# Thermal_MGT.net
KiCad netlist of a schematic drawn in Altium Designer
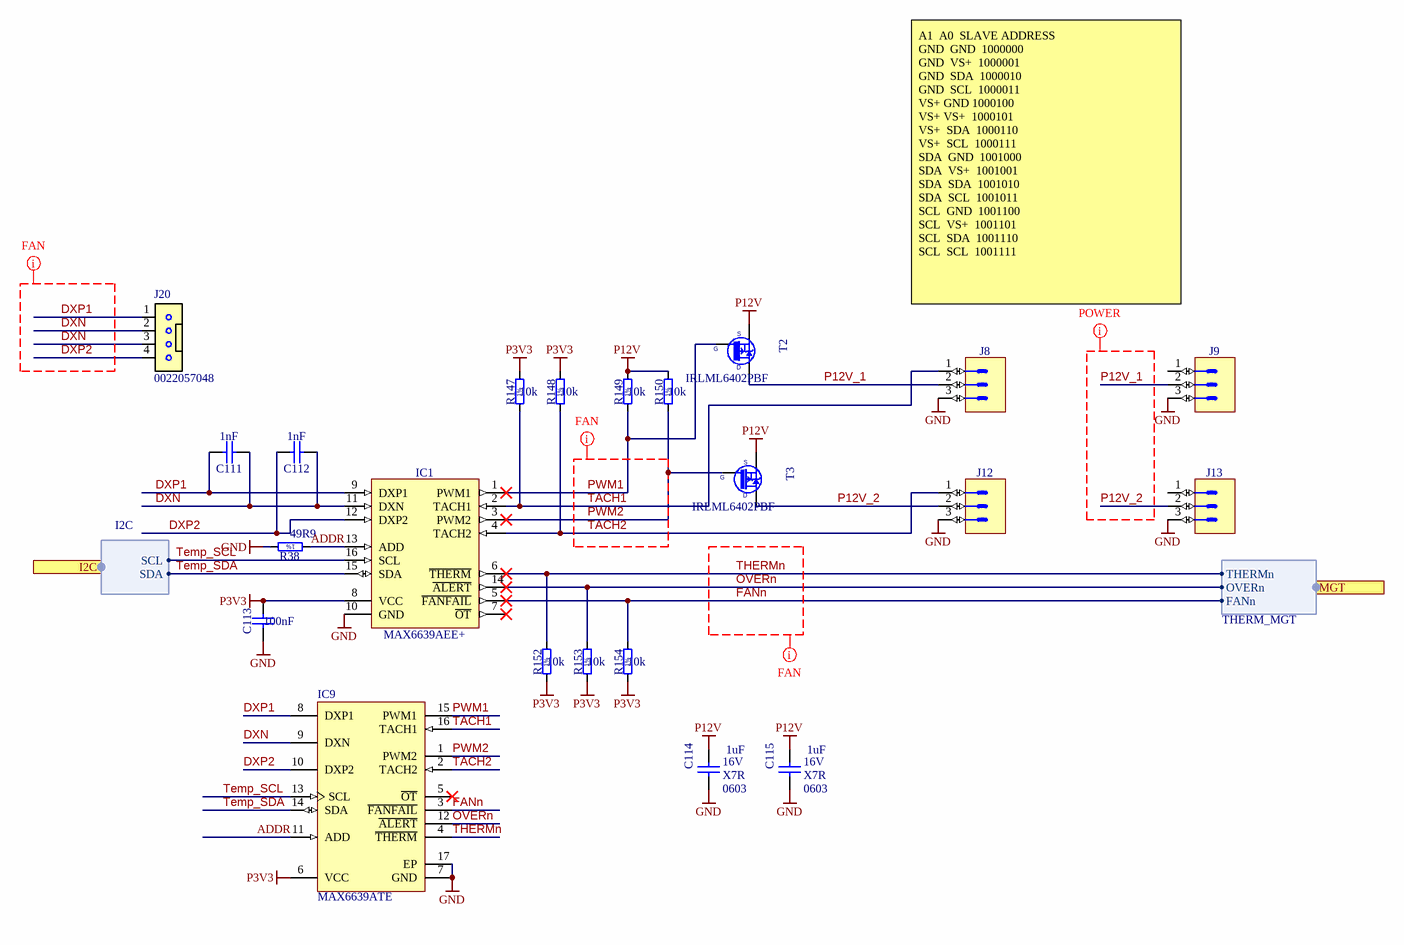
[diagram p0: Thermal_MGT.SchDoc]

(export (version "E")
  (design (tool "Eeschema 10.0.6"))
  (components
    (comp (ref "C111")
      (value "1nF")
      (footprint "CAPC1005X55N")
      (description "Non-polarised capacitor")
      (fields
        (field (name "PART NUMBER") "CC0402_1NF_50V_10%_X7R")
        (field (name "VOLTAGE") "50V")
        (field (name "AUTHOR") "CERN DEM JLC")
      )
      (libsource (lib "Capacitors") (part "Capacitor - non polarized"))
    )
    (comp (ref "C112")
      (value "1nF")
      (footprint "CAPC1005X55N")
      (description "Non-polarised capacitor")
      (fields
        (field (name "PART NUMBER") "CC0402_1NF_50V_10%_X7R")
        (field (name "VOLTAGE") "50V")
        (field (name "AUTHOR") "CERN DEM JLC")
      )
      (libsource (lib "Capacitors") (part "Capacitor - non polarized"))
    )
    (comp (ref "C113")
      (value "100nF")
      (footprint "CAPC1005X55N")
      (description "Non-polarised capacitor")
      (fields
        (field (name "PART NUMBER") "CC0402_100NF_16V_10%_X5R")
        (field (name "VOLTAGE") "16V")
        (field (name "AUTHOR") "CERN DEM JLC")
      )
      (libsource (lib "Capacitors") (part "Capacitor - non polarized"))
    )
    (comp (ref "C114")
      (value "1uF")
      (footprint "CAPC1608X87N")
      (description "Non-polarised capacitor")
      (fields
        (field (name "PART NUMBER") "CC0603_1UF_16V_10%_X7R")
        (field (name "VOLTAGE") "16V")
        (field (name "TC") "X7R")
        (field (name "TOLERANCE") "±10%")
        (field (name "CASE") "0603")
        (field (name "AUTHOR") "CERN DEM JLC")
      )
      (libsource (lib "Capacitors") (part "Capacitor - non polarized"))
    )
    (comp (ref "C115")
      (value "1uF")
      (footprint "CAPC1608X87N")
      (description "Non-polarised capacitor")
      (fields
        (field (name "PART NUMBER") "CC0603_1UF_16V_10%_X7R")
        (field (name "VOLTAGE") "16V")
        (field (name "TC") "X7R")
        (field (name "TOLERANCE") "±10%")
        (field (name "CASE") "0603")
        (field (name "AUTHOR") "CERN DEM JLC")
      )
      (libsource (lib "Capacitors") (part "Capacitor - non polarized"))
    )
    (comp (ref "IC1")
      (value "MAX6639AEE+")
      (footprint "SOP63P600X175-16N")
      (description "2-Channel Temperature Monitor with Dual, Automatic, PWM Fan-Speed Controller")
      (fields (field (name "MANUFACTURER") "MAXIM") (field (name "AUTHOR") "CERN DEM JLC"))
      (libsource (lib "ICs And Semiconductors") (part "MAX6639AEE+"))
    )
    (comp (ref "IC9")
      (value "MAX6639ATE")
      (footprint "MAXM-T1655-3_N")
      (fields (field (name "GENERIC PART NUMBER") "MAX6639"))
      (libsource (lib "Altium Content Vault") (part "MAX6639-T1655X3"))
    )
    (comp (ref "J8")
      (value "KK®")
      (footprint "MOLEX_22-05-7038")
      (description "Connector 3 Male")
      (fields
        (field (name "PART NUMBER") "MOLEX_22-05-7038")
        (field (name "MANUFACTURER") "MOLEX")
        (field (name "AUTHOR") "CERN DEM JLC")
      )
      (libsource (lib "Connectors") (part "Connector 3 Male"))
    )
    (comp (ref "J9")
      (value "KK®")
      (footprint "MOLEX_22-05-7038")
      (description "Connector 3 Male")
      (fields
        (field (name "PART NUMBER") "MOLEX_22-05-7038")
        (field (name "MANUFACTURER") "MOLEX")
        (field (name "AUTHOR") "CERN DEM JLC")
      )
      (libsource (lib "Connectors") (part "Connector 3 Male"))
    )
    (comp (ref "J12")
      (value "KK®")
      (footprint "MOLEX_22-05-7038")
      (description "Connector 3 Male")
      (fields
        (field (name "PART NUMBER") "MOLEX_22-05-7038")
        (field (name "MANUFACTURER") "MOLEX")
        (field (name "AUTHOR") "CERN DEM JLC")
      )
      (libsource (lib "Connectors") (part "Connector 3 Male"))
    )
    (comp (ref "J13")
      (value "KK®")
      (footprint "MOLEX_22-05-7038")
      (description "Connector 3 Male")
      (fields
        (field (name "PART NUMBER") "MOLEX_22-05-7038")
        (field (name "MANUFACTURER") "MOLEX")
        (field (name "AUTHOR") "CERN DEM JLC")
      )
      (libsource (lib "Connectors") (part "Connector 3 Male"))
    )
    (comp (ref "J20")
      (value "0022057048")
      (footprint "CON_0022057048")
      (description "2.54mm crimped terminal header")
      (libsource (lib "Connectors") (part "CON_4_2.54_RA_key"))
    )
    (comp (ref "R38")
      (value "49R9")
      (footprint "RESC1005X40N")
      (description "Resistor - 1%")
      (fields
        (field (name "PART NUMBER") "R0402_49R9_1%_0.0625W_100PPM")
        (field (name "POWER") "0.0625W")
        (field (name "AUTHOR") "CERN DEM JLC")
      )
      (libsource (lib "Resistors") (part "Resistor - 1%"))
    )
    (comp (ref "R147")
      (value "10k")
      (footprint "RESC1005X40N")
      (description "Resistor - 1%")
      (fields
        (field (name "PART NUMBER") "R0402_10K_1%_0.0625W_100PPM")
        (field (name "POWER") "0.0625W")
        (field (name "AUTHOR") "CERN DEM JLC")
      )
      (libsource (lib "Resistors") (part "Resistor - 1%"))
    )
    (comp (ref "R148")
      (value "10k")
      (footprint "RESC1005X40N")
      (description "Resistor - 1%")
      (fields
        (field (name "PART NUMBER") "R0402_10K_1%_0.0625W_100PPM")
        (field (name "POWER") "0.0625W")
        (field (name "AUTHOR") "CERN DEM JLC")
      )
      (libsource (lib "Resistors") (part "Resistor - 1%"))
    )
    (comp (ref "R149")
      (value "10k")
      (footprint "RESC1005X40N")
      (description "Resistor - 1%")
      (fields
        (field (name "PART NUMBER") "R0402_10K_1%_0.0625W_100PPM")
        (field (name "POWER") "0.0625W")
        (field (name "AUTHOR") "CERN DEM JLC")
      )
      (libsource (lib "Resistors") (part "Resistor - 1%"))
    )
    (comp (ref "R150")
      (value "10k")
      (footprint "RESC1005X40N")
      (description "Resistor - 1%")
      (fields
        (field (name "PART NUMBER") "R0402_10K_1%_0.0625W_100PPM")
        (field (name "POWER") "0.0625W")
        (field (name "AUTHOR") "CERN DEM JLC")
      )
      (libsource (lib "Resistors") (part "Resistor - 1%"))
    )
    (comp (ref "R152")
      (value "10k")
      (footprint "RESC1005X40N")
      (description "Resistor - 1%")
      (fields
        (field (name "PART NUMBER") "R0402_10K_1%_0.0625W_100PPM")
        (field (name "POWER") "0.0625W")
        (field (name "AUTHOR") "CERN DEM JLC")
      )
      (libsource (lib "Resistors") (part "Resistor - 1%"))
    )
    (comp (ref "R153")
      (value "10k")
      (footprint "RESC1005X40N")
      (description "Resistor - 1%")
      (fields
        (field (name "PART NUMBER") "R0402_10K_1%_0.0625W_100PPM")
        (field (name "POWER") "0.0625W")
        (field (name "AUTHOR") "CERN DEM JLC")
      )
      (libsource (lib "Resistors") (part "Resistor - 1%"))
    )
    (comp (ref "R154")
      (value "10k")
      (footprint "RESC1005X40N")
      (description "Resistor - 1%")
      (fields
        (field (name "PART NUMBER") "R0402_10K_1%_0.0625W_100PPM")
        (field (name "POWER") "0.0625W")
        (field (name "AUTHOR") "CERN DEM JLC")
      )
      (libsource (lib "Resistors") (part "Resistor - 1%"))
    )
    (comp (ref "T2")
      (value "IRLML6402PBF")
      (footprint "SOT95P237X112-3N")
      (description "P-CHANNEL MOSFET WITH ZENER DIODE")
      (fields (field (name "MANUFACTURER") "INTERNATIONAL RECTIFIER") (field (name "AUTHOR") "CERN DEM JLC"))
      (libsource (lib "ICs And Semiconductors") (part "P-MOSFET-DZ 1G 2S 3D"))
    )
    (comp (ref "T3")
      (value "IRLML6402PBF")
      (footprint "SOT95P237X112-3N")
      (description "P-CHANNEL MOSFET WITH ZENER DIODE")
      (fields (field (name "MANUFACTURER") "INTERNATIONAL RECTIFIER") (field (name "AUTHOR") "CERN DEM JLC"))
      (libsource (lib "ICs And Semiconductors") (part "P-MOSFET-DZ 1G 2S 3D"))
    )
  )
  (nets
    (net (code "3") (name "/ADDR") (class "Default")
      (node (ref "IC1") (pin "13") (pinfunction "ADD_13") (pintype "input"))
      (node (ref "IC9") (pin "11") (pinfunction "ADD_11") (pintype "input"))
      (node (ref "R38") (pin "1") (pinfunction "1_1") (pintype "passive"))
    )
    (net (code "4") (name "/DXN") (class "Default")
      (node (ref "C111") (pin "1") (pinfunction "1_1") (pintype "passive"))
      (node (ref "C112") (pin "1") (pinfunction "1_1") (pintype "passive"))
      (node (ref "IC1") (pin "11") (pinfunction "DXN_11") (pintype "input"))
      (node (ref "IC9") (pin "9") (pinfunction "DXN_9") (pintype "passive"))
      (node (ref "J20") (pin "2") (pinfunction "2_2") (pintype "bidirectional"))
      (node (ref "J20") (pin "3") (pinfunction "3_3") (pintype "bidirectional"))
    )
    (net (code "5") (name "/DXP1") (class "Default")
      (node (ref "C111") (pin "2") (pinfunction "2_2") (pintype "passive"))
      (node (ref "IC1") (pin "9") (pinfunction "DXP1_9") (pintype "input"))
      (node (ref "IC9") (pin "8") (pinfunction "DXP1_8") (pintype "passive"))
      (node (ref "J20") (pin "1") (pinfunction "1_1") (pintype "bidirectional"))
    )
    (net (code "6") (name "/DXP2") (class "Default")
      (node (ref "C112") (pin "2") (pinfunction "2_2") (pintype "passive"))
      (node (ref "IC1") (pin "12") (pinfunction "DXP2_12") (pintype "input"))
      (node (ref "IC9") (pin "10") (pinfunction "DXP2_10") (pintype "passive"))
      (node (ref "J20") (pin "4") (pinfunction "4_4") (pintype "bidirectional"))
    )
    (net (code "7") (name "/FANn") (class "Default")
      (node (ref "IC1") (pin "5") (pinfunction "~{FANFAIL}_5") (pintype "output"))
      (node (ref "IC9") (pin "3") (pinfunction "~{FANFAIL}_3") (pintype "open_collector"))
      (node (ref "R154") (pin "2") (pinfunction "2_2") (pintype "passive"))
    )
    (net (code "8") (name "/OVERn") (class "Default")
      (node (ref "IC1") (pin "14") (pinfunction "~{ALERT}_14") (pintype "output"))
      (node (ref "IC9") (pin "12") (pinfunction "~{ALERT}_12") (pintype "open_collector"))
      (node (ref "R153") (pin "2") (pinfunction "2_2") (pintype "passive"))
    )
    (net (code "9") (name "/P12V_1") (class "Default")
      (node (ref "J8") (pin "2") (pinfunction "2_2") (pintype "bidirectional"))
      (node (ref "J9") (pin "2") (pinfunction "2_2") (pintype "bidirectional"))
      (node (ref "T2") (pin "3") (pinfunction "D_3") (pintype "passive"))
    )
    (net (code "10") (name "/P12V_2") (class "Default")
      (node (ref "J12") (pin "2") (pinfunction "2_2") (pintype "bidirectional"))
      (node (ref "J13") (pin "2") (pinfunction "2_2") (pintype "bidirectional"))
      (node (ref "T3") (pin "3") (pinfunction "D_3") (pintype "passive"))
    )
    (net (code "11") (name "/PWM1") (class "Default")
      (node (ref "IC1") (pin "1") (pinfunction "PWM1_1") (pintype "output"))
      (node (ref "IC9") (pin "15") (pinfunction "PWM1_15") (pintype "open_collector"))
      (node (ref "R149") (pin "1") (pinfunction "1_1") (pintype "passive"))
      (node (ref "T2") (pin "1") (pinfunction "G_1") (pintype "passive"))
    )
    (net (code "12") (name "/PWM2") (class "Default")
      (node (ref "IC1") (pin "3") (pinfunction "PWM2_3") (pintype "output"))
      (node (ref "IC9") (pin "1") (pinfunction "PWM2_1") (pintype "open_collector"))
      (node (ref "R150") (pin "1") (pinfunction "1_1") (pintype "passive"))
      (node (ref "T3") (pin "1") (pinfunction "G_1") (pintype "passive"))
    )
    (net (code "13") (name "/TACH1") (class "Default")
      (node (ref "IC1") (pin "2") (pinfunction "TACH1_2") (pintype "input"))
      (node (ref "IC9") (pin "16") (pinfunction "TACH1_16") (pintype "input"))
      (node (ref "J8") (pin "1") (pinfunction "1_1") (pintype "bidirectional"))
      (node (ref "R147") (pin "1") (pinfunction "1_1") (pintype "passive"))
    )
    (net (code "14") (name "/TACH2") (class "Default")
      (node (ref "IC1") (pin "4") (pinfunction "TACH2_4") (pintype "input"))
      (node (ref "IC9") (pin "2") (pinfunction "TACH2_2") (pintype "input"))
      (node (ref "J12") (pin "1") (pinfunction "1_1") (pintype "bidirectional"))
      (node (ref "R148") (pin "1") (pinfunction "1_1") (pintype "passive"))
    )
    (net (code "15") (name "/THERMn") (class "Default")
      (node (ref "IC1") (pin "6") (pinfunction "~{THERM}_6") (pintype "output"))
      (node (ref "IC9") (pin "4") (pinfunction "~{THERM}_4") (pintype "open_collector"))
      (node (ref "R152") (pin "2") (pinfunction "2_2") (pintype "passive"))
    )
    (net (code "16") (name "/Temp_SCL") (class "Default")
      (node (ref "IC1") (pin "16") (pinfunction "SCL_16") (pintype "input"))
      (node (ref "IC9") (pin "13") (pinfunction "SCL_13") (pintype "input"))
    )
    (net (code "17") (name "/Temp_SDA") (class "Default")
      (node (ref "IC1") (pin "15") (pinfunction "SDA_15") (pintype "bidirectional"))
      (node (ref "IC9") (pin "14") (pinfunction "SDA_14") (pintype "bidirectional"))
    )
    (net (code "20") (name "GND") (class "Default")
      (node (ref "C113") (pin "1") (pinfunction "1_1") (pintype "passive"))
      (node (ref "C114") (pin "1") (pinfunction "1_1") (pintype "passive"))
      (node (ref "C115") (pin "1") (pinfunction "1_1") (pintype "passive"))
      (node (ref "IC1") (pin "10") (pinfunction "GND_10") (pintype "power_in"))
      (node (ref "IC9") (pin "17") (pinfunction "EP_17") (pintype "power_in"))
      (node (ref "IC9") (pin "7") (pinfunction "GND_7") (pintype "power_in"))
      (node (ref "J12") (pin "3") (pinfunction "3_3") (pintype "bidirectional"))
      (node (ref "J13") (pin "3") (pinfunction "3_3") (pintype "bidirectional"))
      (node (ref "J8") (pin "3") (pinfunction "3_3") (pintype "bidirectional"))
      (node (ref "J9") (pin "3") (pinfunction "3_3") (pintype "bidirectional"))
      (node (ref "R38") (pin "2") (pinfunction "2_2") (pintype "passive"))
    )
    (net (code "21") (name "P3V3") (class "Default")
      (node (ref "C113") (pin "2") (pinfunction "2_2") (pintype "passive"))
      (node (ref "IC1") (pin "8") (pinfunction "VCC_8") (pintype "power_in"))
      (node (ref "IC9") (pin "6") (pinfunction "VCC_6") (pintype "power_in"))
      (node (ref "R147") (pin "2") (pinfunction "2_2") (pintype "passive"))
      (node (ref "R148") (pin "2") (pinfunction "2_2") (pintype "passive"))
      (node (ref "R152") (pin "1") (pinfunction "1_1") (pintype "passive"))
      (node (ref "R153") (pin "1") (pinfunction "1_1") (pintype "passive"))
      (node (ref "R154") (pin "1") (pinfunction "1_1") (pintype "passive"))
    )
    (net (code "22") (name "P12V") (class "Default")
      (node (ref "C114") (pin "2") (pinfunction "2_2") (pintype "passive"))
      (node (ref "C115") (pin "2") (pinfunction "2_2") (pintype "passive"))
      (node (ref "R149") (pin "2") (pinfunction "2_2") (pintype "passive"))
      (node (ref "R150") (pin "2") (pinfunction "2_2") (pintype "passive"))
      (node (ref "T2") (pin "2") (pinfunction "S_2") (pintype "passive"))
      (node (ref "T3") (pin "2") (pinfunction "S_2") (pintype "passive"))
    )
    (net (code "23") (name "unconnected-(IC1-~{OT}-Pad7)") (class "Default")
      (node (ref "IC1") (pin "7") (pinfunction "~{OT}_7") (pintype "output+no_connect"))
    )
    (net (code "24") (name "unconnected-(IC9-~{OT}-Pad5)") (class "Default")
      (node (ref "IC9") (pin "5") (pinfunction "~{OT}_5") (pintype "open_collector+no_connect"))
    )
    (net (code "25") (name "unconnected-(J9-Pad1)") (class "Default")
      (node (ref "J9") (pin "1") (pinfunction "1_1") (pintype "bidirectional"))
    )
    (net (code "26") (name "unconnected-(J13-Pad1)") (class "Default")
      (node (ref "J13") (pin "1") (pinfunction "1_1") (pintype "bidirectional"))
    )
  )
)
